# SCH_Mesa_Drivers_2022-08-13.net
KiCad netlist of a schematic drawn in EasyEDA
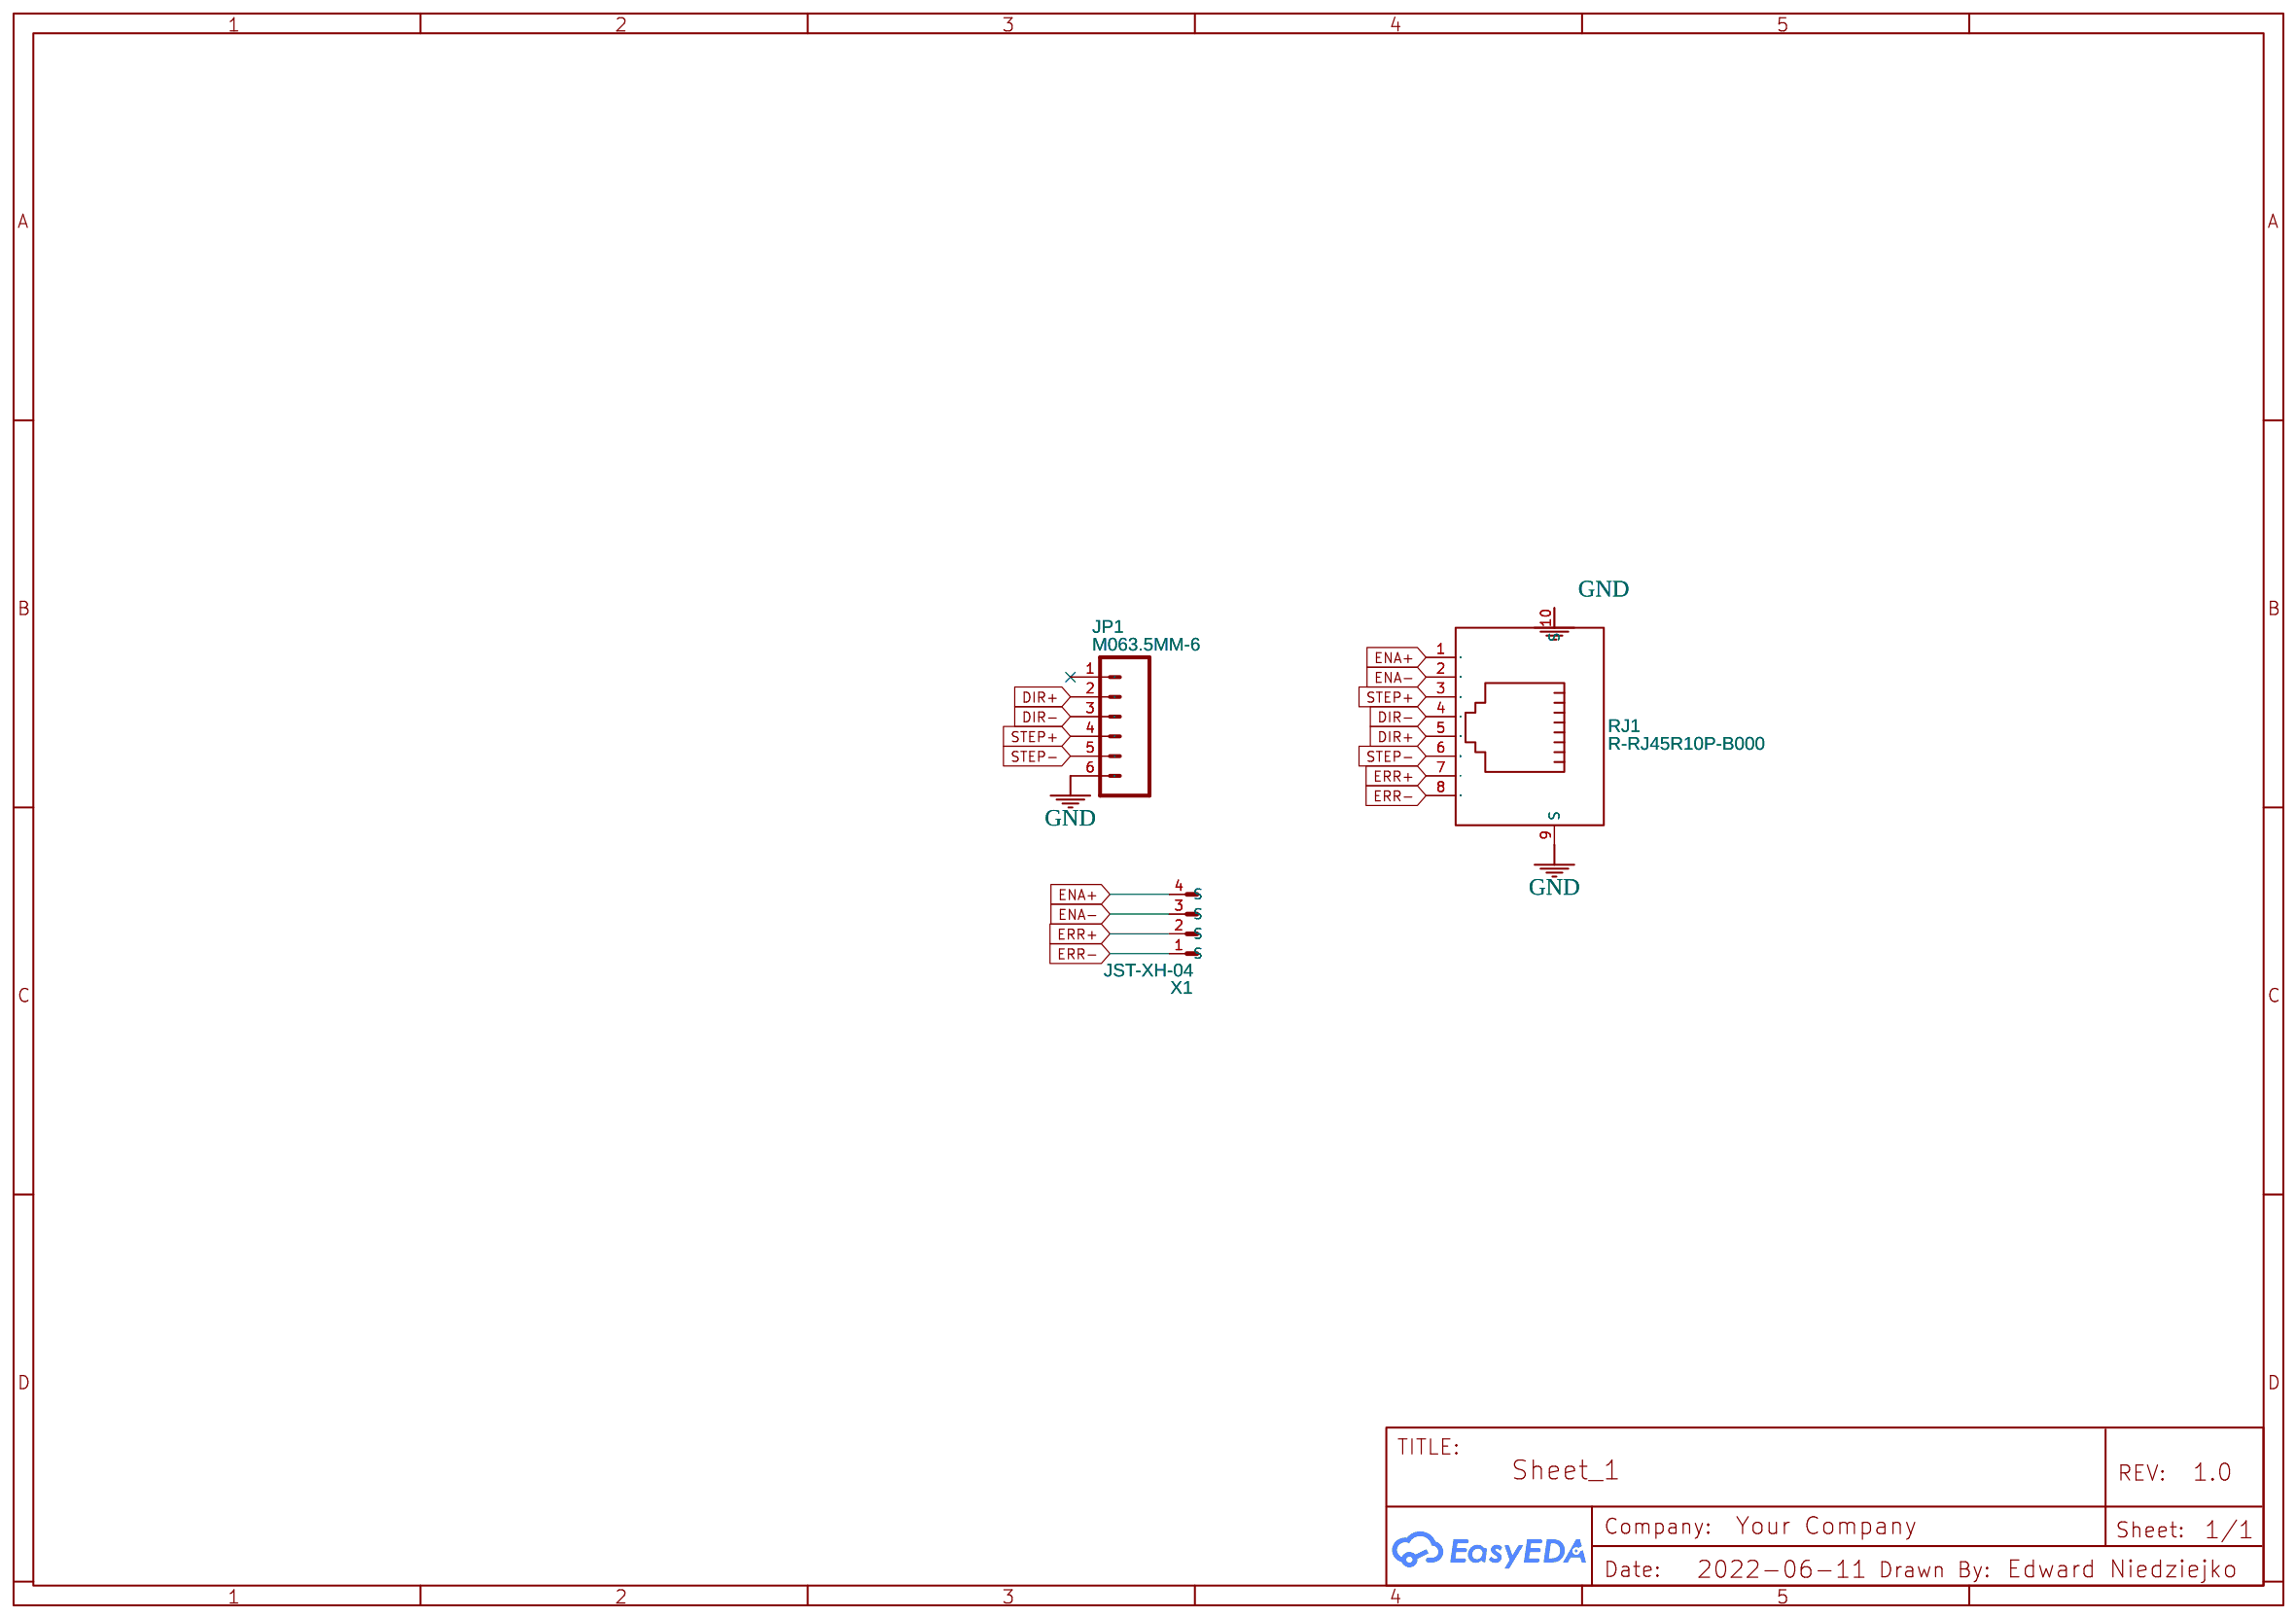
[diagram p0: schematic sheet]

(export (version "E")
  (design (tool "Eeschema 10.0.6"))
  (components
    (comp (ref "JP1") (value "M063.5MM-6") (libsource (lib "") (part "M063.5MM-6")))
    (comp (ref "RJ1")
      (value "R-RJ45R10P-B000")
      (fields (field (name "BOM_Supplier Part") "C386758"))
      (libsource (lib "") (part "R-RJ45R10P-B000"))
    )
    (comp (ref "X1") (value "JST-XH-04") (libsource (lib "") (part "JST-XH-04")))
  )
  (nets
    (net (code "1") (name "DIR+") (class "Default")
      (node (ref "JP1") (pin "2") (pinfunction "2_2") (pintype "unspecified"))
      (node (ref "RJ1") (pin "5") (pinfunction "5_5") (pintype "unspecified"))
    )
    (net (code "2") (name "DIR-") (class "Default")
      (node (ref "JP1") (pin "3") (pinfunction "3_3") (pintype "unspecified"))
      (node (ref "RJ1") (pin "4") (pinfunction "4_4") (pintype "unspecified"))
    )
    (net (code "3") (name "ENA+") (class "Default")
      (node (ref "RJ1") (pin "1") (pinfunction "1_1") (pintype "unspecified"))
      (node (ref "X1") (pin "4") (pinfunction "S_4") (pintype "bidirectional"))
    )
    (net (code "4") (name "ENA-") (class "Default")
      (node (ref "RJ1") (pin "2") (pinfunction "2_2") (pintype "unspecified"))
      (node (ref "X1") (pin "3") (pinfunction "S_3") (pintype "bidirectional"))
    )
    (net (code "5") (name "ERR+") (class "Default")
      (node (ref "RJ1") (pin "7") (pinfunction "7_7") (pintype "unspecified"))
      (node (ref "X1") (pin "2") (pinfunction "S_2") (pintype "bidirectional"))
    )
    (net (code "6") (name "ERR-") (class "Default")
      (node (ref "RJ1") (pin "8") (pinfunction "8_8") (pintype "unspecified"))
      (node (ref "X1") (pin "1") (pinfunction "S_1") (pintype "bidirectional"))
    )
    (net (code "7") (name "GND") (class "Default")
      (node (ref "JP1") (pin "6") (pinfunction "6_6") (pintype "unspecified"))
      (node (ref "RJ1") (pin "10") (pinfunction "S_10") (pintype "unspecified"))
      (node (ref "RJ1") (pin "9") (pinfunction "S_9") (pintype "unspecified"))
    )
    (net (code "8") (name "STEP+") (class "Default")
      (node (ref "JP1") (pin "4") (pinfunction "4_4") (pintype "unspecified"))
      (node (ref "RJ1") (pin "3") (pinfunction "3_3") (pintype "unspecified"))
    )
    (net (code "9") (name "STEP-") (class "Default")
      (node (ref "JP1") (pin "5") (pinfunction "5_5") (pintype "unspecified"))
      (node (ref "RJ1") (pin "6") (pinfunction "6_6") (pintype "unspecified"))
    )
    (net (code "10") (name "unconnected-(JP1-Pad1)") (class "Default")
      (node (ref "JP1") (pin "1") (pinfunction "1_1") (pintype "unspecified+no_connect"))
    )
  )
)
